# layout.net
KiCad netlist of a schematic drawn in EAGLE
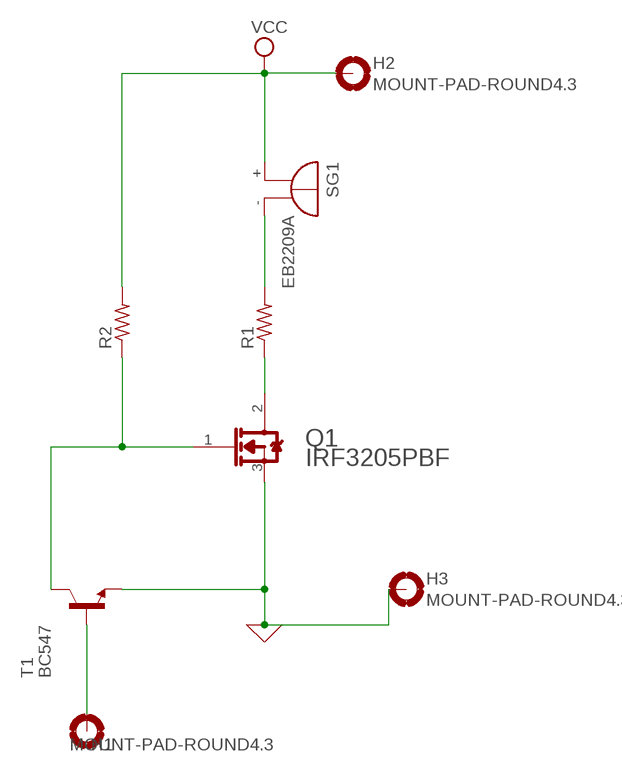
[diagram p0: schematic, sheet 1]

(export (version "E")
  (design (tool "Eeschema 10.0.6"))
  (components
    (comp (ref "H1")
      (value "MOUNT-PAD-ROUND4.3")
      (footprint "eagle-import:4,3-PAD")
      (libsource (lib "eagle-import") (part "MOUNT-PAD-ROUND4.3"))
    )
    (comp (ref "H2")
      (value "MOUNT-PAD-ROUND4.3")
      (footprint "eagle-import:4,3-PAD")
      (libsource (lib "eagle-import") (part "MOUNT-PAD-ROUND4.3"))
    )
    (comp (ref "H3")
      (value "MOUNT-PAD-ROUND4.3")
      (footprint "eagle-import:4,3-PAD")
      (libsource (lib "eagle-import") (part "MOUNT-PAD-ROUND4.3"))
    )
    (comp (ref "Q1")
      (value "INFINEON_IRF3205PBFINFINEON_IRF3205PBF_0_0")
      (footprint "eagle-import:INFINEON_IRF3205PBF_0")
      (fields
        (field (name "DIGIKEY_PART_NUMBER") "IRF3205PBF-ND")
        (field (name "MF") "Infineon")
        (field (name "MOUSER_PART_NUMBER") "942-IRF3205PBF")
      )
      (libsource (lib "eagle-import") (part "INFINEON_IRF3205PBFINFINEON_IRF3205PBF_0_0"))
    )
    (comp (ref "R1")
      (value "R-US_RDH/15")
      (footprint "eagle-import:RDH_15")
      (libsource (lib "eagle-import") (part "R-US_RDH/15"))
    )
    (comp (ref "R2")
      (value "R-US_RDH/15")
      (footprint "eagle-import:RDH_15")
      (libsource (lib "eagle-import") (part "R-US_RDH/15"))
    )
    (comp (ref "SG1")
      (value "EB2209A")
      (footprint "eagle-import:EB2209A")
      (libsource (lib "eagle-import") (part "EB2209A"))
    )
    (comp (ref "T1")
      (value "BC547")
      (footprint "eagle-import:TO92")
      (libsource (lib "eagle-import") (part "BC547"))
    )
  )
  (nets
    (net (code "1") (name "GND") (class "Default")
      (node (ref "H3") (pin "B4,3") (pinfunction "MOUNT_B4,3") (pintype "passive"))
      (node (ref "Q1") (pin "3") (pinfunction "SOURCE_3") (pintype "passive"))
      (node (ref "T1") (pin "1") (pinfunction "E_1") (pintype "passive"))
    )
    (net (code "2") (name "Net-(H1-MOUNT)") (class "Default")
      (node (ref "H1") (pin "B4,3") (pinfunction "MOUNT_B4,3") (pintype "passive"))
      (node (ref "T1") (pin "2") (pinfunction "B_2") (pintype "passive"))
    )
    (net (code "3") (name "Net-(Q1-DRAIN)") (class "Default")
      (node (ref "Q1") (pin "2") (pinfunction "DRAIN_2") (pintype "passive"))
      (node (ref "R1") (pin "1") (pinfunction "1_1") (pintype "passive"))
    )
    (net (code "4") (name "Net-(Q1-GATE)") (class "Default")
      (node (ref "Q1") (pin "1") (pinfunction "GATE_1") (pintype "passive"))
      (node (ref "R2") (pin "1") (pinfunction "1_1") (pintype "passive"))
      (node (ref "T1") (pin "3") (pinfunction "C_3") (pintype "passive"))
    )
    (net (code "5") (name "Net-(R1-Pad2)") (class "Default")
      (node (ref "R1") (pin "2") (pinfunction "2_2") (pintype "passive"))
      (node (ref "SG1") (pin "-") (pinfunction "-_-") (pintype "passive"))
    )
    (net (code "6") (name "VCC") (class "Default")
      (node (ref "H2") (pin "B4,3") (pinfunction "MOUNT_B4,3") (pintype "passive"))
      (node (ref "R2") (pin "2") (pinfunction "2_2") (pintype "passive"))
      (node (ref "SG1") (pin "+") (pinfunction "+_+") (pintype "passive"))
    )
  )
)
